# power_supplies_HVAMP.net
KiCad netlist of a schematic drawn in Altium Designer
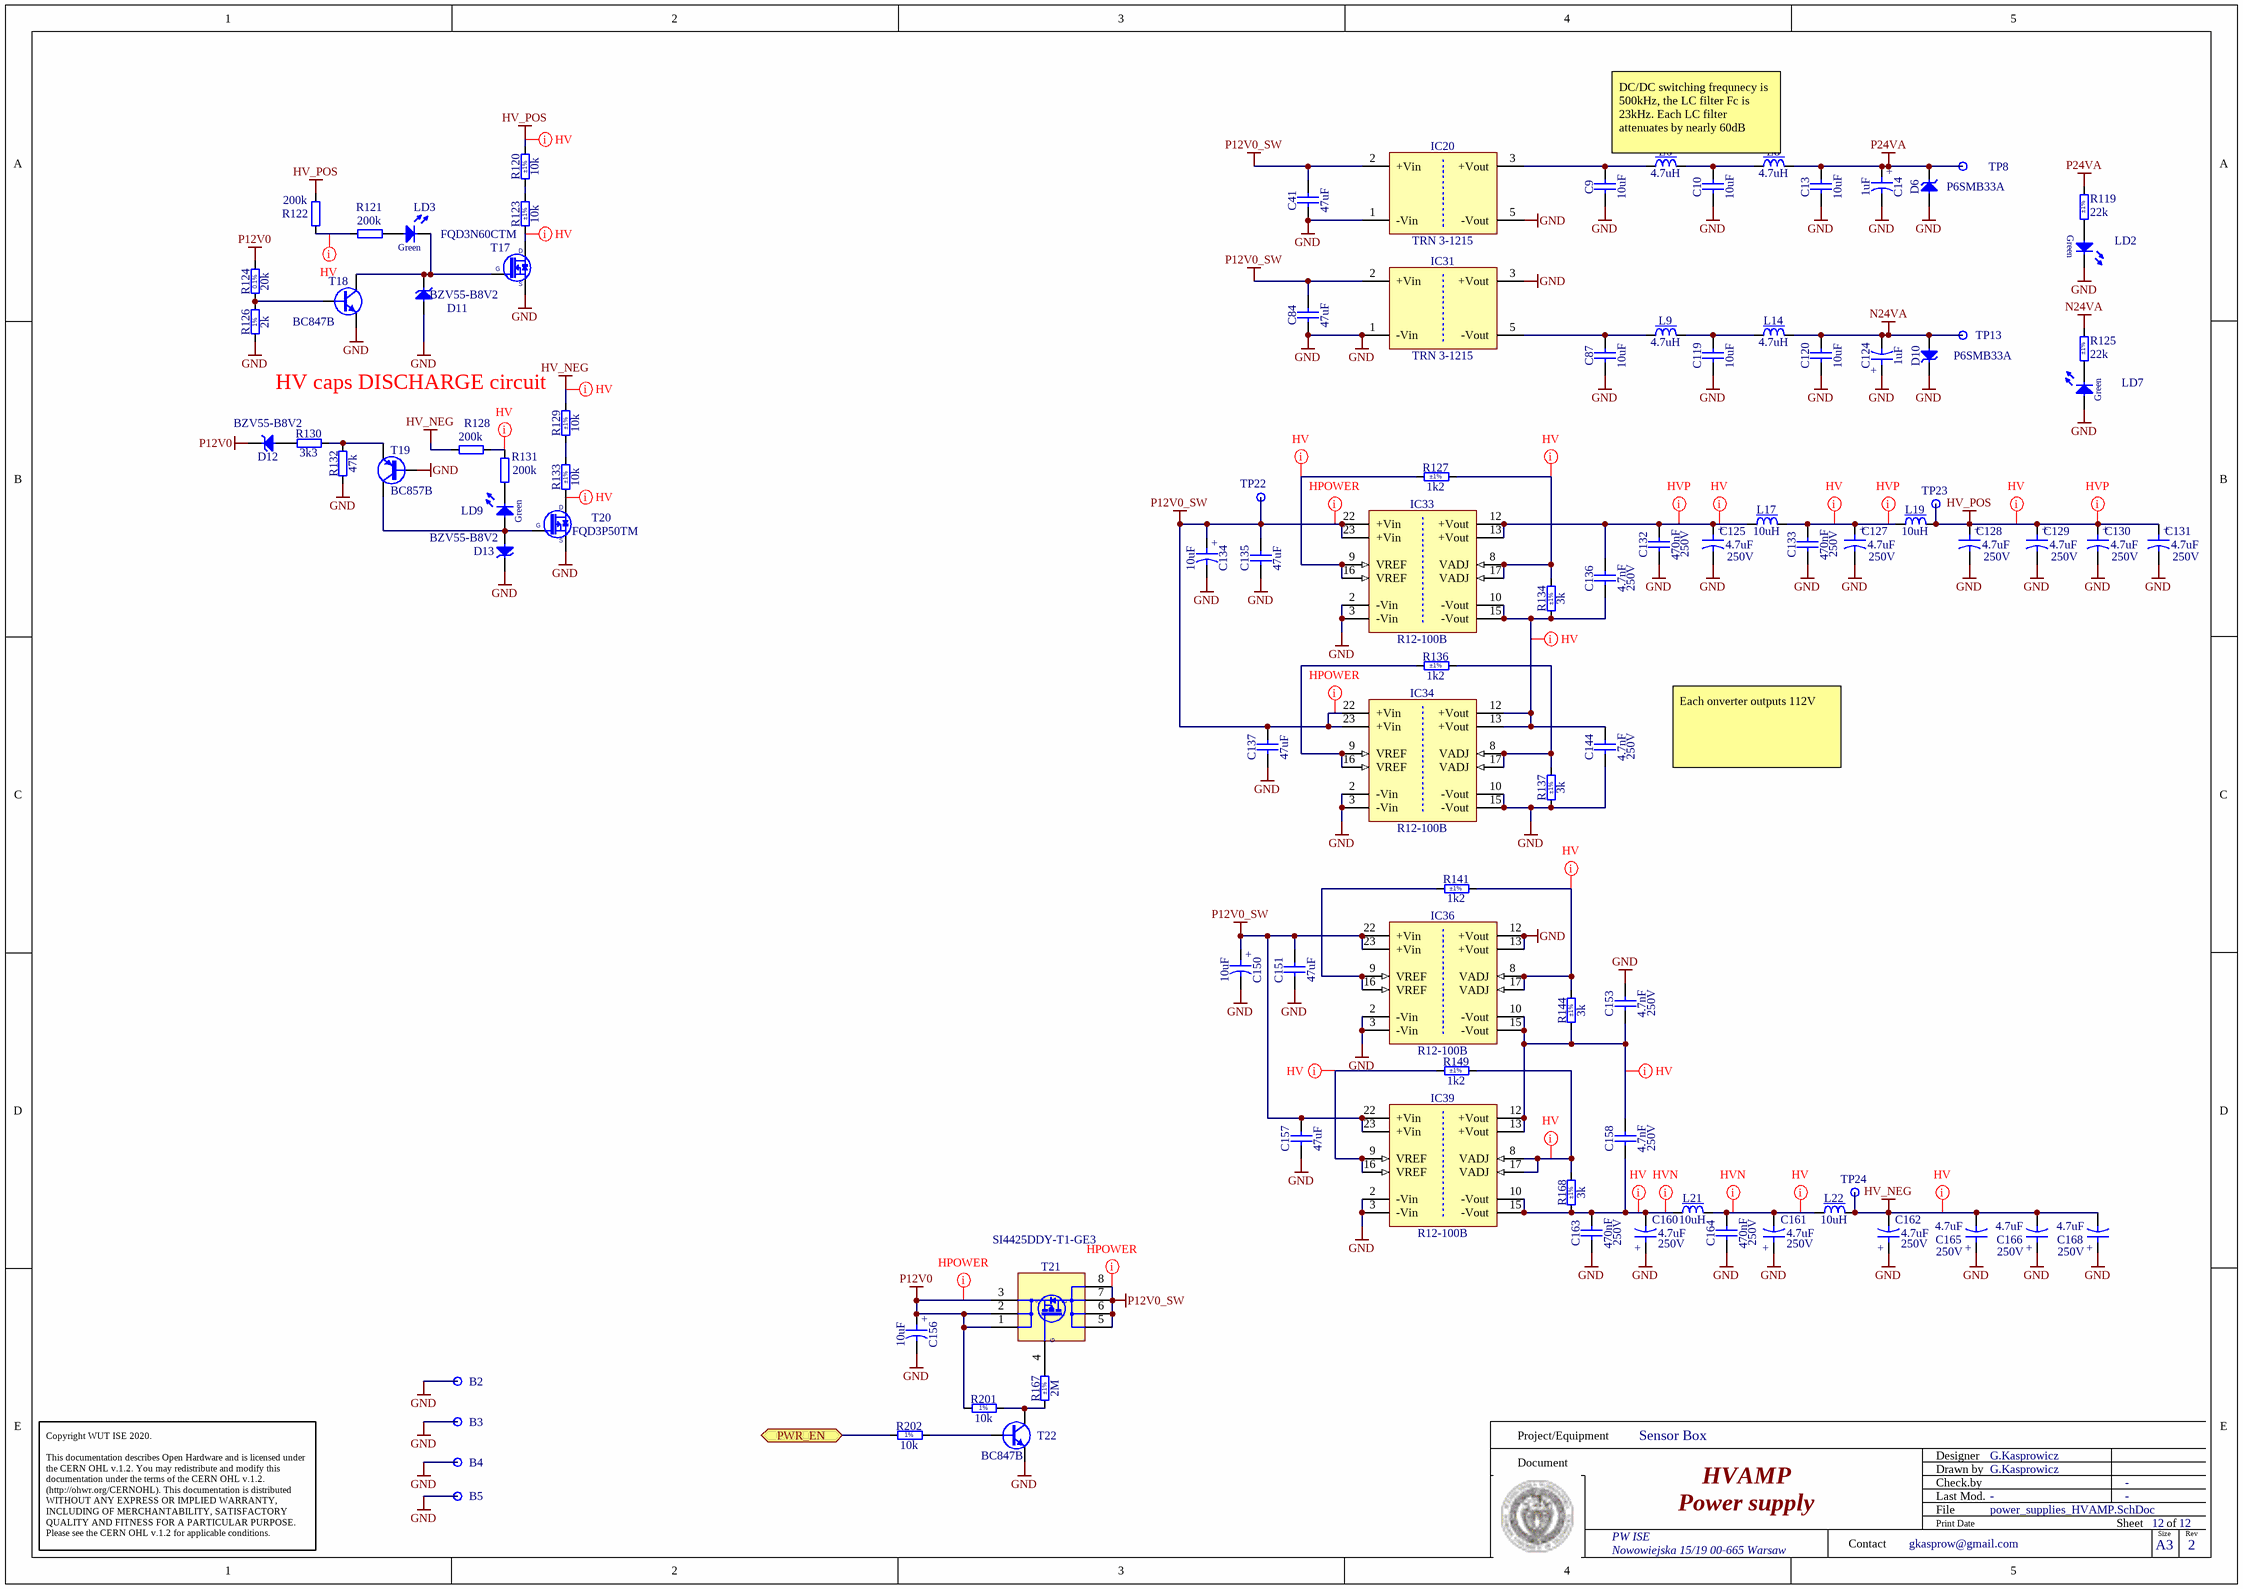
[diagram p0: power_supplies_HVAMP.SchDoc]

(export (version "E")
  (design (tool "Eeschema 10.0.6"))
  (components
    (comp (ref "B2")
      (value "Plated Hole")
      (footprint "MTG320_700")
      (description "Single Terminal Socket")
      (fields (field (name "PART NUMBER") "PLATED_HOLE3.2_PAD7.0"))
      (libsource (lib "Eletro-mechanical") (part "Single Terminal Socket"))
    )
    (comp (ref "B3")
      (value "Plated Hole")
      (footprint "MTG320_700")
      (description "Single Terminal Socket")
      (fields (field (name "PART NUMBER") "PLATED_HOLE3.2_PAD7.0"))
      (libsource (lib "Eletro-mechanical") (part "Single Terminal Socket"))
    )
    (comp (ref "B4")
      (value "Plated Hole")
      (footprint "MTG320_700")
      (description "Single Terminal Socket")
      (fields (field (name "PART NUMBER") "PLATED_HOLE3.2_PAD7.0"))
      (libsource (lib "Eletro-mechanical") (part "Single Terminal Socket"))
    )
    (comp (ref "B5")
      (value "Plated Hole")
      (footprint "MTG320_700")
      (description "Single Terminal Socket")
      (fields (field (name "PART NUMBER") "PLATED_HOLE3.2_PAD7.0"))
      (libsource (lib "Eletro-mechanical") (part "Single Terminal Socket"))
    )
    (comp (ref "C9")
      (value "10uF")
      (footprint "CAPC2012X145N")
      (description "Non-polarised capacitor")
      (fields
        (field (name "PART NUMBER") "CC0805_10UF_35V_10%_X5R_MURATA_GRM21BR6YA106KE43L")
        (field (name "VOLTAGE") "35V")
      )
      (libsource (lib "Capacitors") (part "Capacitor - non polarized"))
    )
    (comp (ref "C10")
      (value "10uF")
      (footprint "CAPC2012X145N")
      (description "Non-polarised capacitor")
      (fields
        (field (name "PART NUMBER") "CC0805_10UF_35V_10%_X5R_MURATA_GRM21BR6YA106KE43L")
        (field (name "VOLTAGE") "35V")
      )
      (libsource (lib "Capacitors") (part "Capacitor - non polarized"))
    )
    (comp (ref "C13")
      (value "10uF")
      (footprint "CAPC2012X145N")
      (description "Non-polarised capacitor")
      (fields
        (field (name "PART NUMBER") "CC0805_10UF_35V_10%_X5R_MURATA_GRM21BR6YA106KE43L")
        (field (name "VOLTAGE") "35V")
      )
      (libsource (lib "Capacitors") (part "Capacitor - non polarized"))
    )
    (comp (ref "C14")
      (value "1uF")
      (footprint "CAPMP3216X180N")
      (description "Polarised capacitor")
      (fields (field (name "PART NUMBER") "CTE3216-18_1UF_35V_10%") (field (name "VOLTAGE") "35V"))
      (libsource (lib "Capacitors") (part "Capacitor - polarized"))
    )
    (comp (ref "C41")
      (value "47uF")
      (footprint "CAPC3225X270N")
      (description "Non-polarised capacitor")
      (fields (field (name "PART NUMBER") "CC1210_47UF_16V_20%_X5R") (field (name "VOLTAGE") "16V"))
      (libsource (lib "Capacitors") (part "Capacitor - non polarized"))
    )
    (comp (ref "C84")
      (value "47uF")
      (footprint "CAPC3225X270N")
      (description "Non-polarised capacitor")
      (fields (field (name "PART NUMBER") "CC1210_47UF_16V_20%_X5R") (field (name "VOLTAGE") "16V"))
      (libsource (lib "Capacitors") (part "Capacitor - non polarized"))
    )
    (comp (ref "C87")
      (value "10uF")
      (footprint "CAPC2012X145N")
      (description "Non-polarised capacitor")
      (fields
        (field (name "PART NUMBER") "CC0805_10UF_35V_10%_X5R_MURATA_GRM21BR6YA106KE43L")
        (field (name "VOLTAGE") "35V")
      )
      (libsource (lib "Capacitors") (part "Capacitor - non polarized"))
    )
    (comp (ref "C119")
      (value "10uF")
      (footprint "CAPC2012X145N")
      (description "Non-polarised capacitor")
      (fields
        (field (name "PART NUMBER") "CC0805_10UF_35V_10%_X5R_MURATA_GRM21BR6YA106KE43L")
        (field (name "VOLTAGE") "35V")
      )
      (libsource (lib "Capacitors") (part "Capacitor - non polarized"))
    )
    (comp (ref "C120")
      (value "10uF")
      (footprint "CAPC2012X145N")
      (description "Non-polarised capacitor")
      (fields
        (field (name "PART NUMBER") "CC0805_10UF_35V_10%_X5R_MURATA_GRM21BR6YA106KE43L")
        (field (name "VOLTAGE") "35V")
      )
      (libsource (lib "Capacitors") (part "Capacitor - non polarized"))
    )
    (comp (ref "C124")
      (value "1uF")
      (footprint "CAPMP3216X180N")
      (description "Polarised capacitor")
      (fields (field (name "PART NUMBER") "CTE3216-18_1UF_35V_10%") (field (name "VOLTAGE") "35V"))
      (libsource (lib "Capacitors") (part "Capacitor - polarized"))
    )
    (comp (ref "C125")
      (value "4.7uF")
      (footprint "CAPAE9383X100M")
      (description "Electrolytic capacitor 4.7uF 250V")
      (fields
        (field (name "PART NUMBER") "CAE800-1000_4.7UF_250V_20%")
        (field (name "VOLTAGE") "250V")
        (field (name "TOLERANCE") "±20%")
      )
      (libsource (lib "Passives_RC") (part "CAP_ELECTRO_F_4.7u_250V"))
    )
    (comp (ref "C127")
      (value "4.7uF")
      (footprint "CAPAE9383X100M")
      (description "Electrolytic capacitor 4.7uF 250V")
      (fields
        (field (name "PART NUMBER") "CAE800-1000_4.7UF_250V_20%")
        (field (name "VOLTAGE") "250V")
        (field (name "TOLERANCE") "±20%")
      )
      (libsource (lib "Passives_RC") (part "CAP_ELECTRO_F_4.7u_250V"))
    )
    (comp (ref "C128")
      (value "4.7uF")
      (footprint "CAPAE9383X100M")
      (description "Electrolytic capacitor 4.7uF 250V")
      (fields
        (field (name "PART NUMBER") "CAE800-1000_4.7UF_250V_20%")
        (field (name "VOLTAGE") "250V")
        (field (name "TOLERANCE") "±20%")
      )
      (libsource (lib "Passives_RC") (part "CAP_ELECTRO_F_4.7u_250V"))
    )
    (comp (ref "C129")
      (value "4.7uF")
      (footprint "CAPAE9383X100M")
      (description "Electrolytic capacitor 4.7uF 250V")
      (fields
        (field (name "PART NUMBER") "CAE800-1000_4.7UF_250V_20%")
        (field (name "VOLTAGE") "250V")
        (field (name "TOLERANCE") "±20%")
      )
      (libsource (lib "Passives_RC") (part "CAP_ELECTRO_F_4.7u_250V"))
    )
    (comp (ref "C130")
      (value "4.7uF")
      (footprint "CAPAE9383X100M")
      (description "Electrolytic capacitor 4.7uF 250V")
      (fields
        (field (name "PART NUMBER") "CAE800-1000_4.7UF_250V_20%")
        (field (name "VOLTAGE") "250V")
        (field (name "TOLERANCE") "±20%")
      )
      (libsource (lib "Passives_RC") (part "CAP_ELECTRO_F_4.7u_250V"))
    )
    (comp (ref "C131")
      (value "4.7uF")
      (footprint "CAPAE9383X100M")
      (description "Electrolytic capacitor 4.7uF 250V")
      (fields
        (field (name "PART NUMBER") "CAE800-1000_4.7UF_250V_20%")
        (field (name "VOLTAGE") "250V")
        (field (name "TOLERANCE") "±20%")
      )
      (libsource (lib "Passives_RC") (part "CAP_ELECTRO_F_4.7u_250V"))
    )
    (comp (ref "C132")
      (value "470nF")
      (footprint "CAPC4532X185N")
      (description "Non-polarised capacitor")
      (fields
        (field (name "PART NUMBER") "CC1812_470NF_250V_10%_X7R_FT-CAP")
        (field (name "VOLTAGE") "250V")
        (field (name "TOLERANCE") "±10%")
      )
      (libsource (lib "Capacitors") (part "Capacitor - non polarized"))
    )
    (comp (ref "C133")
      (value "470nF")
      (footprint "CAPC4532X185N")
      (description "Non-polarised capacitor")
      (fields
        (field (name "PART NUMBER") "CC1812_470NF_250V_10%_X7R_FT-CAP")
        (field (name "VOLTAGE") "250V")
        (field (name "TOLERANCE") "±10%")
      )
      (libsource (lib "Capacitors") (part "Capacitor - non polarized"))
    )
    (comp (ref "C134")
      (value "10uF")
      (footprint "CAPMP6032X280N")
      (description "Polarised capacitor")
      (fields (field (name "PART NUMBER") "CTE6032-28_10UF_25V_10%_LESR0500") (field (name "VOLTAGE") "25V"))
      (libsource (lib "Capacitors") (part "Capacitor - polarized"))
    )
    (comp (ref "C135")
      (value "47uF")
      (footprint "CAPC3225X270N")
      (description "Non-polarised capacitor")
      (fields (field (name "PART NUMBER") "CC1210_47UF_16V_20%_X5R") (field (name "VOLTAGE") "16V"))
      (libsource (lib "Capacitors") (part "Capacitor - non polarized"))
    )
    (comp (ref "C136")
      (value "4.7nF")
      (footprint "CAPC2012X135N")
      (description "Non-polarised capacitor")
      (fields
        (field (name "PART NUMBER") "CC0805_4.7NF_250V_10%_X7R")
        (field (name "VOLTAGE") "250V")
        (field (name "TOLERANCE") "±10%")
      )
      (libsource (lib "Capacitors") (part "Capacitor - non polarized"))
    )
    (comp (ref "C137")
      (value "47uF")
      (footprint "CAPC3225X270N")
      (description "Non-polarised capacitor")
      (fields (field (name "PART NUMBER") "CC1210_47UF_16V_20%_X5R") (field (name "VOLTAGE") "16V"))
      (libsource (lib "Capacitors") (part "Capacitor - non polarized"))
    )
    (comp (ref "C144")
      (value "4.7nF")
      (footprint "CAPC2012X135N")
      (description "Non-polarised capacitor")
      (fields
        (field (name "PART NUMBER") "CC0805_4.7NF_250V_10%_X7R")
        (field (name "VOLTAGE") "250V")
        (field (name "TOLERANCE") "±10%")
      )
      (libsource (lib "Capacitors") (part "Capacitor - non polarized"))
    )
    (comp (ref "C150")
      (value "10uF")
      (footprint "CAPMP6032X280N")
      (description "Polarised capacitor")
      (fields (field (name "PART NUMBER") "CTE6032-28_10UF_25V_10%_LESR0500") (field (name "VOLTAGE") "25V"))
      (libsource (lib "Capacitors") (part "Capacitor - polarized"))
    )
    (comp (ref "C151")
      (value "47uF")
      (footprint "CAPC3225X270N")
      (description "Non-polarised capacitor")
      (fields (field (name "PART NUMBER") "CC1210_47UF_16V_20%_X5R") (field (name "VOLTAGE") "16V"))
      (libsource (lib "Capacitors") (part "Capacitor - non polarized"))
    )
    (comp (ref "C153")
      (value "4.7nF")
      (footprint "CAPC2012X135N")
      (description "Non-polarised capacitor")
      (fields
        (field (name "PART NUMBER") "CC0805_4.7NF_250V_10%_X7R")
        (field (name "VOLTAGE") "250V")
        (field (name "TOLERANCE") "±10%")
      )
      (libsource (lib "Capacitors") (part "Capacitor - non polarized"))
    )
    (comp (ref "C156")
      (value "10uF")
      (footprint "CAPMP6032X280N")
      (description "Polarised capacitor")
      (fields (field (name "PART NUMBER") "CTE6032-28_10UF_25V_10%_LESR0500") (field (name "VOLTAGE") "25V"))
      (libsource (lib "Capacitors") (part "Capacitor - polarized"))
    )
    (comp (ref "C157")
      (value "47uF")
      (footprint "CAPC3225X270N")
      (description "Non-polarised capacitor")
      (fields (field (name "PART NUMBER") "CC1210_47UF_16V_20%_X5R") (field (name "VOLTAGE") "16V"))
      (libsource (lib "Capacitors") (part "Capacitor - non polarized"))
    )
    (comp (ref "C158")
      (value "4.7nF")
      (footprint "CAPC2012X135N")
      (description "Non-polarised capacitor")
      (fields
        (field (name "PART NUMBER") "CC0805_4.7NF_250V_10%_X7R")
        (field (name "VOLTAGE") "250V")
        (field (name "TOLERANCE") "±10%")
      )
      (libsource (lib "Capacitors") (part "Capacitor - non polarized"))
    )
    (comp (ref "C160")
      (value "4.7uF")
      (footprint "CAPAE9383X100M")
      (description "Electrolytic capacitor 4.7uF 250V")
      (fields
        (field (name "PART NUMBER") "CAE800-1000_4.7UF_250V_20%")
        (field (name "VOLTAGE") "250V")
        (field (name "TOLERANCE") "±20%")
      )
      (libsource (lib "Passives_RC") (part "CAP_ELECTRO_F_4.7u_250V"))
    )
    (comp (ref "C161")
      (value "4.7uF")
      (footprint "CAPAE9383X100M")
      (description "Electrolytic capacitor 4.7uF 250V")
      (fields
        (field (name "PART NUMBER") "CAE800-1000_4.7UF_250V_20%")
        (field (name "VOLTAGE") "250V")
        (field (name "TOLERANCE") "±20%")
      )
      (libsource (lib "Passives_RC") (part "CAP_ELECTRO_F_4.7u_250V"))
    )
    (comp (ref "C162")
      (value "4.7uF")
      (footprint "CAPAE9383X100M")
      (description "Electrolytic capacitor 4.7uF 250V")
      (fields
        (field (name "PART NUMBER") "CAE800-1000_4.7UF_250V_20%")
        (field (name "VOLTAGE") "250V")
        (field (name "TOLERANCE") "±20%")
      )
      (libsource (lib "Passives_RC") (part "CAP_ELECTRO_F_4.7u_250V"))
    )
    (comp (ref "C163")
      (value "470nF")
      (footprint "CAPC4532X185N")
      (description "Non-polarised capacitor")
      (fields
        (field (name "PART NUMBER") "CC1812_470NF_250V_10%_X7R_FT-CAP")
        (field (name "VOLTAGE") "250V")
        (field (name "TOLERANCE") "±10%")
      )
      (libsource (lib "Capacitors") (part "Capacitor - non polarized"))
    )
    (comp (ref "C164")
      (value "470nF")
      (footprint "CAPC4532X185N")
      (description "Non-polarised capacitor")
      (fields
        (field (name "PART NUMBER") "CC1812_470NF_250V_10%_X7R_FT-CAP")
        (field (name "VOLTAGE") "250V")
        (field (name "TOLERANCE") "±10%")
      )
      (libsource (lib "Capacitors") (part "Capacitor - non polarized"))
    )
    (comp (ref "C165")
      (value "4.7uF")
      (footprint "CAPAE9383X100M")
      (description "Electrolytic capacitor 4.7uF 250V")
      (fields
        (field (name "PART NUMBER") "CAE800-1000_4.7UF_250V_20%")
        (field (name "VOLTAGE") "250V")
        (field (name "TOLERANCE") "±20%")
      )
      (libsource (lib "Passives_RC") (part "CAP_ELECTRO_F_4.7u_250V"))
    )
    (comp (ref "C166")
      (value "4.7uF")
      (footprint "CAPAE9383X100M")
      (description "Electrolytic capacitor 4.7uF 250V")
      (fields
        (field (name "PART NUMBER") "CAE800-1000_4.7UF_250V_20%")
        (field (name "VOLTAGE") "250V")
        (field (name "TOLERANCE") "±20%")
      )
      (libsource (lib "Passives_RC") (part "CAP_ELECTRO_F_4.7u_250V"))
    )
    (comp (ref "C168")
      (value "4.7uF")
      (footprint "CAPAE9383X100M")
      (description "Electrolytic capacitor 4.7uF 250V")
      (fields
        (field (name "PART NUMBER") "CAE800-1000_4.7UF_250V_20%")
        (field (name "VOLTAGE") "250V")
        (field (name "TOLERANCE") "±20%")
      )
      (libsource (lib "Passives_RC") (part "CAP_ELECTRO_F_4.7u_250V"))
    )
    (comp (ref "D6")
      (value "P6SMB33A")
      (footprint "DIOM5436X261N")
      (description "Transient Voltage Suppressor Diode (Uni-Directional)")
      (fields (field (name "VOLTAGE") "33V") (field (name "POWER") "600W"))
      (libsource (lib "ICs And Semiconductors") (part "Diode TVS Uni-Directional"))
    )
    (comp (ref "D10")
      (value "P6SMB33A")
      (footprint "DIOM5436X261N")
      (description "Transient Voltage Suppressor Diode (Uni-Directional)")
      (fields (field (name "VOLTAGE") "33V") (field (name "POWER") "600W"))
      (libsource (lib "ICs And Semiconductors") (part "Diode TVS Uni-Directional"))
    )
    (comp (ref "D11")
      (value "BZV55-B8V2")
      (footprint "DIOMELF3515N")
      (description "Zener Diode")
      (fields (field (name "VOLTAGE") "8V2") (field (name "POWER") "500mW"))
      (libsource (lib "ICs And Semiconductors") (part "Diode Zener"))
    )
    (comp (ref "D12")
      (value "BZV55-B8V2")
      (footprint "DIOMELF3515N")
      (description "Zener Diode")
      (fields (field (name "VOLTAGE") "8V2") (field (name "POWER") "500mW"))
      (libsource (lib "ICs And Semiconductors") (part "Diode Zener"))
    )
    (comp (ref "D13")
      (value "BZV55-B8V2")
      (footprint "DIOMELF3515N")
      (description "Zener Diode")
      (fields (field (name "VOLTAGE") "8V2") (field (name "POWER") "500mW"))
      (libsource (lib "ICs And Semiconductors") (part "Diode Zener"))
    )
    (comp (ref "IC20")
      (value "TRN 3-1215")
      (footprint "DCDC_TRACO_TRN3")
      (description "9-18V DC to 24V, Iout (max) 125mA, 3W DC-DC Converter")
      (fields (field (name "MANUFACTURER") "TRACO POWER"))
      (libsource (lib "Regulators_SMPS") (part "DCDC_TRACO_TRN 3-0515"))
    )
    (comp (ref "IC31")
      (value "TRN 3-1215")
      (footprint "DCDC_TRACO_TRN3")
      (description "9-18V DC to 24V, Iout (max) 125mA, 3W DC-DC Converter")
      (fields (field (name "MANUFACTURER") "TRACO POWER"))
      (libsource (lib "Regulators_SMPS") (part "DCDC_TRACO_TRN 3-0515"))
    )
    (comp (ref "IC33")
      (value "R12-100B")
      (footprint "DCDC_RECOM_Rxx-B")
      (description "RECOM, Rxx-B Series, Single Output DCDC Converter")
      (fields (field (name "MANUFACTURER") "RECOM"))
      (libsource (lib "ICs And Semiconductors") (part "DCDC_RECOM_Rxx-B_Single Output"))
    )
    (comp (ref "IC34")
      (value "R12-100B")
      (footprint "DCDC_RECOM_Rxx-B")
      (description "RECOM, Rxx-B Series, Single Output DCDC Converter")
      (fields (field (name "MANUFACTURER") "RECOM"))
      (libsource (lib "ICs And Semiconductors") (part "DCDC_RECOM_Rxx-B_Single Output"))
    )
    (comp (ref "IC36")
      (value "R12-100B")
      (footprint "DCDC_RECOM_Rxx-B")
      (description "RECOM, Rxx-B Series, Single Output DCDC Converter")
      (fields (field (name "MANUFACTURER") "RECOM"))
      (libsource (lib "ICs And Semiconductors") (part "DCDC_RECOM_Rxx-B_Single Output"))
    )
    (comp (ref "IC39")
      (value "R12-100B")
      (footprint "DCDC_RECOM_Rxx-B")
      (description "RECOM, Rxx-B Series, Single Output DCDC Converter")
      (fields (field (name "MANUFACTURER") "RECOM"))
      (libsource (lib "ICs And Semiconductors") (part "DCDC_RECOM_Rxx-B_Single Output"))
    )
    (comp (ref "L6")
      (value "4.7uH")
      (footprint "INDC2012X145N")
      (description "Inductor With Core")
      (fields (field (name "PART NUMBER") "IND0805_4.7UH_20%_TAIYO-YUDEN_CB") (field (name "POWER") "300mA"))
      (libsource (lib "Inductors & Transformers") (part "Inductor With Magnetic core"))
    )
    (comp (ref "L8")
      (value "4.7uH")
      (footprint "INDC2012X145N")
      (description "Inductor With Core")
      (fields (field (name "PART NUMBER") "IND0805_4.7UH_20%_TAIYO-YUDEN_CB") (field (name "POWER") "300mA"))
      (libsource (lib "Inductors & Transformers") (part "Inductor With Magnetic core"))
    )
    (comp (ref "L9")
      (value "4.7uH")
      (footprint "INDC2012X145N")
      (description "Inductor With Core")
      (fields (field (name "PART NUMBER") "IND0805_4.7UH_20%_TAIYO-YUDEN_CB") (field (name "POWER") "300mA"))
      (libsource (lib "Inductors & Transformers") (part "Inductor With Magnetic core"))
    )
    (comp (ref "L14")
      (value "4.7uH")
      (footprint "INDC2012X145N")
      (description "Inductor With Core")
      (fields (field (name "PART NUMBER") "IND0805_4.7UH_20%_TAIYO-YUDEN_CB") (field (name "POWER") "300mA"))
      (libsource (lib "Inductors & Transformers") (part "Inductor With Magnetic core"))
    )
    (comp (ref "L17")
      (value "10uH")
      (footprint "IND_MURATA-PS_8400")
      (description "Inductor With Core")
      (fields (field (name "PART NUMBER") "IND_10UH_10%_MURATA-PS_8400") (field (name "POWER") "950mA"))
      (libsource (lib "Inductors & Transformers") (part "Inductor With Magnetic core"))
    )
    (comp (ref "L19")
      (value "10uH")
      (footprint "IND_MURATA-PS_8400")
      (description "Inductor With Core")
      (fields (field (name "PART NUMBER") "IND_10UH_10%_MURATA-PS_8400") (field (name "POWER") "950mA"))
      (libsource (lib "Inductors & Transformers") (part "Inductor With Magnetic core"))
    )
    (comp (ref "L21")
      (value "10uH")
      (footprint "IND_MURATA-PS_8400")
      (description "Inductor With Core")
      (fields (field (name "PART NUMBER") "IND_10UH_10%_MURATA-PS_8400") (field (name "POWER") "950mA"))
      (libsource (lib "Inductors & Transformers") (part "Inductor With Magnetic core"))
    )
    (comp (ref "L22")
      (value "10uH")
      (footprint "IND_MURATA-PS_8400")
      (description "Inductor With Core")
      (fields (field (name "PART NUMBER") "IND_10UH_10%_MURATA-PS_8400") (field (name "POWER") "950mA"))
      (libsource (lib "Inductors & Transformers") (part "Inductor With Magnetic core"))
    )
    (comp (ref "LD2")
      (value "Green")
      (footprint "LED_KINGBRIGHT_KPH-1608CGCKr")
      (description "Green 0603")
      (fields
        (field (name "PART NUMBER") "LED_KINGBRIGHT_KPH-1608CGCK")
        (field (name "MANUFACTURER") "KINGBRIGHT")
      )
      (libsource (lib "LIBRARY_SCH") (part "LED_0603_Green"))
    )
    (comp (ref "LD3")
      (value "Green")
      (footprint "LED_KINGBRIGHT_KPH-1608CGCKr")
      (description "Green 0603")
      (fields
        (field (name "PART NUMBER") "LED_KINGBRIGHT_KPH-1608CGCK")
        (field (name "MANUFACTURER") "KINGBRIGHT")
      )
      (libsource (lib "LIBRARY_SCH") (part "LED_0603_Green"))
    )
    (comp (ref "LD7")
      (value "Green")
      (footprint "LED_KINGBRIGHT_KPH-1608CGCKr")
      (description "Green 0603")
      (fields
        (field (name "PART NUMBER") "LED_KINGBRIGHT_KPH-1608CGCK")
        (field (name "MANUFACTURER") "KINGBRIGHT")
      )
      (libsource (lib "LIBRARY_SCH") (part "LED_0603_Green"))
    )
    (comp (ref "LD9")
      (value "Green")
      (footprint "LED_KINGBRIGHT_KPH-1608CGCKr")
      (description "Green 0603")
      (fields
        (field (name "PART NUMBER") "LED_KINGBRIGHT_KPH-1608CGCK")
        (field (name "MANUFACTURER") "KINGBRIGHT")
      )
      (libsource (lib "LIBRARY_SCH") (part "LED_0603_Green"))
    )
    (comp (ref "R119")
      (value "22k")
      (footprint "RESC1005X40N")
      (description "Resistor - 1%")
      (fields
        (field (name "PART NUMBER") "R0402_22K_1%_0.0625W_100PPM")
        (field (name "POWER") "0.0625W")
        (field (name "TOLERANCE") "±1%")
      )
      (libsource (lib "Resistors") (part "Resistor - 1%"))
    )
    (comp (ref "R120")
      (value "10k")
      (footprint "RESC3216X65N")
      (description "Resistor - 1%")
      (fields
        (field (name "TOLERANCE") "±1%")
        (field (name "PART NUMBER") "R1206_10K_1%_0.25W_100PPM")
        (field (name "POWER") "0.25W")
      )
      (libsource (lib "Resistors") (part "Resistor - 1%"))
    )
    (comp (ref "R121")
      (value "200k")
      (footprint "RESC3216X65N")
      (description "Resistor - 1%")
      (fields (field (name "PART NUMBER") "R1206_200K_1%_0.25W_100PPM") (field (name "POWER") "0.25W"))
      (libsource (lib "Resistors") (part "Resistor - 1%"))
    )
    (comp (ref "R122")
      (value "200k")
      (footprint "RESC3216X65N")
      (description "Resistor - 1%")
      (fields (field (name "PART NUMBER") "R1206_200K_1%_0.25W_100PPM") (field (name "POWER") "0.25W"))
      (libsource (lib "Resistors") (part "Resistor - 1%"))
    )
    (comp (ref "R123")
      (value "10k")
      (footprint "RESC3216X65N")
      (description "Resistor - 1%")
      (fields
        (field (name "TOLERANCE") "±1%")
        (field (name "PART NUMBER") "R1206_10K_1%_0.25W_100PPM")
        (field (name "POWER") "0.25W")
      )
      (libsource (lib "Resistors") (part "Resistor - 1%"))
    )
    (comp (ref "R124")
      (value "20k")
      (footprint "RESC1608X55N")
      (description "Resistor - 0.1%")
      (fields (field (name "PART NUMBER") "R0603_20K_0.1%_0.063W_10PPM") (field (name "POWER") "0.063W"))
      (libsource (lib "Resistors") (part "Resistor - 0.1%"))
    )
    (comp (ref "R125")
      (value "22k")
      (footprint "RESC1005X40N")
      (description "Resistor - 1%")
      (fields
        (field (name "PART NUMBER") "R0402_22K_1%_0.0625W_100PPM")
        (field (name "POWER") "0.0625W")
        (field (name "TOLERANCE") "±1%")
      )
      (libsource (lib "Resistors") (part "Resistor - 1%"))
    )
    (comp (ref "R126")
      (value "2k")
      (footprint "RESC1005X40N")
      (description "Resistor - 1%")
      (fields (field (name "PART NUMBER") "R0402_2K_1%_0.0625W_100PPM") (field (name "POWER") "0.0625W"))
      (libsource (lib "") (part "Resistor - 1%_1"))
    )
    (comp (ref "R127")
      (value "1k2")
      (footprint "RESC1608X55N")
      (description "Resistor - 1%")
      (fields
        (field (name "TOLERANCE") "±1%")
        (field (name "PART NUMBER") "R0603_1K2_1%_0.1W_100PPM")
        (field (name "POWER") "0.1W")
      )
      (libsource (lib "Resistors") (part "Resistor - 1%"))
    )
    (comp (ref "R128")
      (value "200k")
      (footprint "RESC3216X65N")
      (description "Resistor - 1%")
      (fields (field (name "PART NUMBER") "R1206_200K_1%_0.25W_100PPM") (field (name "POWER") "0.25W"))
      (libsource (lib "Resistors") (part "Resistor - 1%"))
    )
    (comp (ref "R129")
      (value "10k")
      (footprint "RESC3216X65N")
      (description "Resistor - 1%")
      (fields
        (field (name "TOLERANCE") "±1%")
        (field (name "PART NUMBER") "R1206_10K_1%_0.25W_100PPM")
        (field (name "POWER") "0.25W")
      )
      (libsource (lib "Resistors") (part "Resistor - 1%"))
    )
    (comp (ref "R130")
      (value "3k3")
      (footprint "RESC1005X40N")
      (description "Resistor - 1%")
      (fields (field (name "PART NUMBER") "R0402_3K3_1%_0.0625W_100PPM") (field (name "POWER") "0.0625W"))
      (libsource (lib "Resistors") (part "Resistor - 1%"))
    )
    (comp (ref "R131")
      (value "200k")
      (footprint "RESC3216X65N")
      (description "Resistor - 1%")
      (fields (field (name "PART NUMBER") "R1206_200K_1%_0.25W_100PPM") (field (name "POWER") "0.25W"))
      (libsource (lib "Resistors") (part "Resistor - 1%"))
    )
    (comp (ref "R132")
      (value "47k")
      (footprint "RESC1608X55N")
      (description "Resistor - 1%")
      (fields (field (name "PART NUMBER") "R0603_47K_1%_0.1W_100PPM") (field (name "POWER") "0.1W"))
      (libsource (lib "Resistors") (part "Resistor - 1%"))
    )
    (comp (ref "R133")
      (value "10k")
      (footprint "RESC3216X65N")
      (description "Resistor - 1%")
      (fields
        (field (name "TOLERANCE") "±1%")
        (field (name "PART NUMBER") "R1206_10K_1%_0.25W_100PPM")
        (field (name "POWER") "0.25W")
      )
      (libsource (lib "Resistors") (part "Resistor - 1%"))
    )
    (comp (ref "R134")
      (value "3k")
      (footprint "RESC1608X55N")
      (description "Resistor - 1%")
      (fields
        (field (name "TOLERANCE") "±1%")
        (field (name "PART NUMBER") "R0603_3K_1%_0.1W_100PPM")
        (field (name "POWER") "0.1W")
      )
      (libsource (lib "Resistors") (part "Resistor - 1%"))
    )
    (comp (ref "R136")
      (value "1k2")
      (footprint "RESC1608X55N")
      (description "Resistor - 1%")
      (fields
        (field (name "TOLERANCE") "±1%")
        (field (name "PART NUMBER") "R0603_1K2_1%_0.1W_100PPM")
        (field (name "POWER") "0.1W")
      )
      (libsource (lib "Resistors") (part "Resistor - 1%"))
    )
    (comp (ref "R137")
      (value "3k")
      (footprint "RESC1608X55N")
      (description "Resistor - 1%")
      (fields
        (field (name "TOLERANCE") "±1%")
        (field (name "PART NUMBER") "R0603_3K_1%_0.1W_100PPM")
        (field (name "POWER") "0.1W")
      )
      (libsource (lib "Resistors") (part "Resistor - 1%"))
    )
    (comp (ref "R141")
      (value "1k2")
      (footprint "RESC1608X55N")
      (description "Resistor - 1%")
      (fields
        (field (name "TOLERANCE") "±1%")
        (field (name "PART NUMBER") "R0603_1K2_1%_0.1W_100PPM")
        (field (name "POWER") "0.1W")
      )
      (libsource (lib "Resistors") (part "Resistor - 1%"))
    )
    (comp (ref "R144")
      (value "3k")
      (footprint "RESC1608X55N")
      (description "Resistor - 1%")
      (fields
        (field (name "TOLERANCE") "±1%")
        (field (name "PART NUMBER") "R0603_3K_1%_0.1W_100PPM")
        (field (name "POWER") "0.1W")
      )
      (libsource (lib "Resistors") (part "Resistor - 1%"))
    )
    (comp (ref "R149")
      (value "1k2")
      (footprint "RESC1608X55N")
      (description "Resistor - 1%")
      (fields
        (field (name "TOLERANCE") "±1%")
        (field (name "PART NUMBER") "R0603_1K2_1%_0.1W_100PPM")
        (field (name "POWER") "0.1W")
      )
      (libsource (lib "Resistors") (part "Resistor - 1%"))
    )
    (comp (ref "R167")
      (value "2M")
      (footprint "RESC1005X40N")
      (description "Resistor - 1%")
      (fields
        (field (name "TOLERANCE") "±1%")
        (field (name "PART NUMBER") "R0402_2M_1%_0.0625W_100PPM")
        (field (name "POWER") "0.0625W")
      )
      (libsource (lib "Resistors") (part "Resistor - 1%"))
    )
    (comp (ref "R168")
      (value "3k")
      (footprint "RESC1608X55N")
      (description "Resistor - 1%")
      (fields
        (field (name "TOLERANCE") "±1%")
        (field (name "PART NUMBER") "R0603_3K_1%_0.1W_100PPM")
        (field (name "POWER") "0.1W")
      )
      (libsource (lib "Resistors") (part "Resistor - 1%"))
    )
    (comp (ref "R201")
      (value "10k")
      (footprint "RESC1005X40N")
      (description "Resistor - 1%")
      (fields (field (name "PART NUMBER") "R0402_10K_1%_0.0625W_100PPM") (field (name "POWER") "0.0625W"))
      (libsource (lib "") (part "Resistor - 1%_1"))
    )
    (comp (ref "R202")
      (value "10k")
      (footprint "RESC1005X40N")
      (description "Resistor - 1%")
      (fields (field (name "PART NUMBER") "R0402_10K_1%_0.0625W_100PPM") (field (name "POWER") "0.0625W"))
      (libsource (lib "") (part "Resistor - 1%_1"))
    )
    (comp (ref "T17")
      (value "FQD3N60CTM")
      (footprint "TO228P991X239-3N-R552X520")
      (description "N-CHANNEL 600V, 2.4A, 3.4Ohm")
      (fields (field (name "MANUFACTURER") "ONSEMI"))
      (libsource (lib "Tranistors_Thyristors") (part "Q_FQD3N60CTM"))
    )
    (comp (ref "T18")
      (value "BC847B")
      (footprint "SOT95P230X110-3N")
      (description "NPN Transistor")
      (fields (field (name "MANUFACTURER") "NXP SEMICONDUCTORS"))
      (libsource (lib "ICs And Semiconductors") (part "NPN B1 E2 C3"))
    )
    (comp (ref "T19")
      (value "BC857B")
      (footprint "SOT95P230X110-3N")
      (description "PNP Transistor")
      (fields (field (name "MANUFACTURER") "NXP SEMICONDUCTORS"))
      (libsource (lib "ICs And Semiconductors") (part "PNP B1 E2 C3"))
    )
    (comp (ref "T20")
      (value "FQD3P50TM")
      (footprint "TO228P991X239-3N-R552X520")
      (description "P-CHANNEL -500V, -2.1A 4.9Ohm")
      (fields (field (name "MANUFACTURER") "ONSEMI"))
      (libsource (lib "Tranistors_Thyristors") (part "Q_FQD3P50TM"))
    )
    (comp (ref "T21")
      (value "SI4425DDY-T1-GE3")
      (footprint "SOIC127P600X175-8N")
      (description "-30V -19.7A P-Channel MOSFET")
      (fields (field (name "MANUFACTURER") "VISHAY SILICONIX"))
      (libsource (lib "ICs And Semiconductors") (part "SI4425DDY"))
    )
    (comp (ref "T22")
      (value "BC847B")
      (footprint "SOT95P230X110-3N")
      (description "NPN Transistor")
      (fields (field (name "MANUFACTURER") "NXP SEMICONDUCTORS"))
      (libsource (lib "ICs And Semiconductors") (part "NPN B1 E2 C3"))
    )
    (comp (ref "TP8")
      (value "Test Point")
      (footprint "TPS127")
      (fields (field (name "PART NUMBER") "SMD_PAD_1.27X1.27MM"))
      (libsource (lib "Eletro-mechanical") (part "Test Point"))
    )
    (comp (ref "TP13")
      (value "Test Point")
      (footprint "TPS127")
      (fields (field (name "PART NUMBER") "SMD_PAD_1.27X1.27MM"))
      (libsource (lib "Eletro-mechanical") (part "Test Point"))
    )
    (comp (ref "TP22")
      (value "Test Point")
      (footprint "TPS127")
      (fields (field (name "PART NUMBER") "SMD_PAD_1.27X1.27MM"))
      (libsource (lib "Eletro-mechanical") (part "Test Point"))
    )
    (comp (ref "TP23")
      (value "Test Point")
      (footprint "TPS127")
      (fields (field (name "PART NUMBER") "SMD_PAD_1.27X1.27MM"))
      (libsource (lib "Eletro-mechanical") (part "Test Point"))
    )
    (comp (ref "TP24")
      (value "Test Point")
      (footprint "TPS127")
      (fields (field (name "PART NUMBER") "SMD_PAD_1.27X1.27MM"))
      (libsource (lib "Eletro-mechanical") (part "Test Point"))
    )
  )
  (nets
    (net (code "1") (name "/PWR_EN") (class "Default")
      (node (ref "R202") (pin "1") (pinfunction "1_1") (pintype "passive"))
    )
    (net (code "2") (name "GND") (class "Default")
      (node (ref "B2") (pin "1") (pinfunction "1_1") (pintype "bidirectional"))
      (node (ref "B3") (pin "1") (pinfunction "1_1") (pintype "bidirectional"))
      (node (ref "B4") (pin "1") (pinfunction "1_1") (pintype "bidirectional"))
      (node (ref "B5") (pin "1") (pinfunction "1_1") (pintype "bidirectional"))
      (node (ref "C10") (pin "1") (pinfunction "1_1") (pintype "passive"))
      (node (ref "C119") (pin "1") (pinfunction "1_1") (pintype "passive"))
      (node (ref "C120") (pin "1") (pinfunction "1_1") (pintype "passive"))
      (node (ref "C124") (pin "1") (pinfunction "1_1") (pintype "passive"))
      (node (ref "C125") (pin "2") (pinfunction "2_2") (pintype "passive"))
      (node (ref "C127") (pin "2") (pinfunction "2_2") (pintype "passive"))
      (node (ref "C128") (pin "2") (pinfunction "2_2") (pintype "passive"))
      (node (ref "C129") (pin "2") (pinfunction "2_2") (pintype "passive"))
      (node (ref "C13") (pin "1") (pinfunction "1_1") (pintype "passive"))
      (node (ref "C130") (pin "2") (pinfunction "2_2") (pintype "passive"))
      (node (ref "C131") (pin "2") (pinfunction "2_2") (pintype "passive"))
      (node (ref "C132") (pin "1") (pinfunction "1_1") (pintype "passive"))
      (node (ref "C133") (pin "1") (pinfunction "1_1") (pintype "passive"))
      (node (ref "C134") (pin "2") (pinfunction "2_2") (pintype "passive"))
      (node (ref "C135") (pin "1") (pinfunction "1_1") (pintype "passive"))
      (node (ref "C137") (pin "1") (pinfunction "1_1") (pintype "passive"))
      (node (ref "C14") (pin "2") (pinfunction "2_2") (pintype "passive"))
      (node (ref "C144") (pin "1") (pinfunction "1_1") (pintype "passive"))
      (node (ref "C150") (pin "2") (pinfunction "2_2") (pintype "passive"))
      (node (ref "C151") (pin "1") (pinfunction "1_1") (pintype "passive"))
      (node (ref "C153") (pin "2") (pinfunction "2_2") (pintype "passive"))
      (node (ref "C156") (pin "2") (pinfunction "2_2") (pintype "passive"))
      (node (ref "C157") (pin "1") (pinfunction "1_1") (pintype "passive"))
      (node (ref "C160") (pin "1") (pinfunction "1_1") (pintype "passive"))
      (node (ref "C161") (pin "1") (pinfunction "1_1") (pintype "passive"))
      (node (ref "C162") (pin "1") (pinfunction "1_1") (pintype "passive"))
      (node (ref "C163") (pin "1") (pinfunction "1_1") (pintype "passive"))
      (node (ref "C164") (pin "1") (pinfunction "1_1") (pintype "passive"))
      (node (ref "C165") (pin "1") (pinfunction "1_1") (pintype "passive"))
      (node (ref "C166") (pin "1") (pinfunction "1_1") (pintype "passive"))
      (node (ref "C168") (pin "1") (pinfunction "1_1") (pintype "passive"))
      (node (ref "C41") (pin "1") (pinfunction "1_1") (pintype "passive"))
      (node (ref "C84") (pin "1") (pinfunction "1_1") (pintype "passive"))
      (node (ref "C87") (pin "1") (pinfunction "1_1") (pintype "passive"))
      (node (ref "C9") (pin "1") (pinfunction "1_1") (pintype "passive"))
      (node (ref "D10") (pin "1") (pinfunction "C_1") (pintype "passive"))
      (node (ref "D11") (pin "2") (pinfunction "A_2") (pintype "passive"))
      (node (ref "D13") (pin "1") (pinfunction "C_1") (pintype "passive"))
      (node (ref "D6") (pin "2") (pinfunction "A_2") (pintype "passive"))
      (node (ref "IC20") (pin "1") (pinfunction "-Vin_1") (pintype "power_in"))
      (node (ref "IC20") (pin "5") (pinfunction "-Vout_5") (pintype "power_in"))
      (node (ref "IC31") (pin "1") (pinfunction "-Vin_1") (pintype "power_in"))
      (node (ref "IC31") (pin "3") (pinfunction "+Vout_3") (pintype "power_in"))
      (node (ref "IC33") (pin "2") (pinfunction "-Vin_2") (pintype "power_in"))
      (node (ref "IC33") (pin "3") (pinfunction "-Vin_3") (pintype "power_in"))
      (node (ref "IC34") (pin "10") (pinfunction "-Vout_10") (pintype "power_in"))
      (node (ref "IC34") (pin "15") (pinfunction "-Vout_15") (pintype "power_in"))
      (node (ref "IC34") (pin "2") (pinfunction "-Vin_2") (pintype "power_in"))
      (node (ref "IC34") (pin "3") (pinfunction "-Vin_3") (pintype "power_in"))
      (node (ref "IC36") (pin "12") (pinfunction "+Vout_12") (pintype "power_in"))
      (node (ref "IC36") (pin "13") (pinfunction "+Vout_13") (pintype "power_in"))
      (node (ref "IC36") (pin "2") (pinfunction "-Vin_2") (pintype "power_in"))
      (node (ref "IC36") (pin "3") (pinfunction "-Vin_3") (pintype "power_in"))
      (node (ref "IC39") (pin "2") (pinfunction "-Vin_2") (pintype "power_in"))
      (node (ref "IC39") (pin "3") (pinfunction "-Vin_3") (pintype "power_in"))
      (node (ref "LD2") (pin "1") (pinfunction "C_1") (pintype "passive"))
      (node (ref "LD7") (pin "2") (pinfunction "A_2") (pintype "passive"))
      (node (ref "R126") (pin "1") (pinfunction "1_1") (pintype "passive"))
      (node (ref "R132") (pin "1") (pinfunction "1_1") (pintype "passive"))
      (node (ref "R137") (pin "1") (pinfunction "1_1") (pintype "passive"))
      (node (ref "T17") (pin "2") (pinfunction "S_2") (pintype "passive"))
      (node (ref "T18") (pin "2") (pinfunction "E_2") (pintype "passive"))
      (node (ref "T19") (pin "1") (pinfunction "B_1") (pintype "passive"))
      (node (ref "T20") (pin "2") (pinfunction "S_2") (pintype "passive"))
      (node (ref "T22") (pin "2") (pinfunction "E_2") (pintype "passive"))
    )
    (net (code "3") (name "HV_NEG") (class "Default")
      (node (ref "C162") (pin "2") (pinfunction "2_2") (pintype "passive"))
      (node (ref "C165") (pin "2") (pinfunction "2_2") (pintype "passive"))
      (node (ref "C166") (pin "2") (pinfunction "2_2") (pintype "passive"))
      (node (ref "C168") (pin "2") (pinfunction "2_2") (pintype "passive"))
      (node (ref "L22") (pin "2") (pinfunction "2_2") (pintype "passive"))
      (node (ref "R128") (pin "1") (pinfunction "1_1") (pintype "passive"))
      (node (ref "R129") (pin "2") (pinfunction "2_2") (pintype "passive"))
      (node (ref "TP24") (pin "1") (pinfunction "1_1") (pintype "bidirectional"))
    )
    (net (code "4") (name "HV_POS") (class "Default")
      (node (ref "C128") (pin "1") (pinfunction "1_1") (pintype "passive"))
      (node (ref "C129") (pin "1") (pinfunction "1_1") (pintype "passive"))
      (node (ref "C130") (pin "1") (pinfunction "1_1") (pintype "passive"))
      (node (ref "C131") (pin "1") (pinfunction "1_1") (pintype "passive"))
      (node (ref "L19") (pin "2") (pinfunction "2_2") (pintype "passive"))
      (node (ref "R120") (pin "2") (pinfunction "2_2") (pintype "passive"))
      (node (ref "R122") (pin "2") (pinfunction "2_2") (pintype "passive"))
      (node (ref "TP23") (pin "1") (pinfunction "1_1") (pintype "bidirectional"))
    )
    (net (code "5") (name "N24VA") (class "Default")
      (node (ref "C120") (pin "2") (pinfunction "2_2") (pintype "passive"))
      (node (ref "C124") (pin "2") (pinfunction "2_2") (pintype "passive"))
      (node (ref "D10") (pin "2") (pinfunction "A_2") (pintype "passive"))
      (node (ref "L14") (pin "2") (pinfunction "2_2") (pintype "passive"))
      (node (ref "R125") (pin "2") (pinfunction "2_2") (pintype "passive"))
      (node (ref "TP13") (pin "1") (pinfunction "1_1") (pintype "bidirectional"))
    )
    (net (code "6") (name "Net-(C10-Pad2)") (class "Default")
      (node (ref "C10") (pin "2") (pinfunction "2_2") (pintype "passive"))
      (node (ref "L6") (pin "2") (pinfunction "2_2") (pintype "passive"))
      (node (ref "L8") (pin "1") (pinfunction "1_1") (pintype "passive"))
    )
    (net (code "7") (name "Net-(C119-Pad2)") (class "Default")
      (node (ref "C119") (pin "2") (pinfunction "2_2") (pintype "passive"))
      (node (ref "L14") (pin "1") (pinfunction "1_1") (pintype "passive"))
      (node (ref "L9") (pin "2") (pinfunction "2_2") (pintype "passive"))
    )
    (net (code "8") (name "Net-(C125-Pad1)") (class "Default")
      (node (ref "C125") (pin "1") (pinfunction "1_1") (pintype "passive"))
      (node (ref "C132") (pin "2") (pinfunction "2_2") (pintype "passive"))
      (node (ref "C136") (pin "2") (pinfunction "2_2") (pintype "passive"))
      (node (ref "IC33") (pin "12") (pinfunction "+Vout_12") (pintype "power_in"))
      (node (ref "IC33") (pin "13") (pinfunction "+Vout_13") (pintype "power_in"))
      (node (ref "L17") (pin "1") (pinfunction "1_1") (pintype "passive"))
    )
    (net (code "9") (name "Net-(C127-Pad1)") (class "Default")
      (node (ref "C127") (pin "1") (pinfunction "1_1") (pintype "passive"))
      (node (ref "C133") (pin "2") (pinfunction "2_2") (pintype "passive"))
      (node (ref "L17") (pin "2") (pinfunction "2_2") (pintype "passive"))
      (node (ref "L19") (pin "1") (pinfunction "1_1") (pintype "passive"))
    )
    (net (code "10") (name "Net-(C136-Pad1)") (class "Default")
      (node (ref "C136") (pin "1") (pinfunction "1_1") (pintype "passive"))
      (node (ref "C144") (pin "2") (pinfunction "2_2") (pintype "passive"))
      (node (ref "IC33") (pin "10") (pinfunction "-Vout_10") (pintype "power_in"))
      (node (ref "IC33") (pin "15") (pinfunction "-Vout_15") (pintype "power_in"))
      (node (ref "IC34") (pin "12") (pinfunction "+Vout_12") (pintype "power_in"))
      (node (ref "IC34") (pin "13") (pinfunction "+Vout_13") (pintype "power_in"))
      (node (ref "R134") (pin "1") (pinfunction "1_1") (pintype "passive"))
    )
    (net (code "11") (name "Net-(C153-Pad1)") (class "Default")
      (node (ref "C153") (pin "1") (pinfunction "1_1") (pintype "passive"))
      (node (ref "C158") (pin "2") (pinfunction "2_2") (pintype "passive"))
      (node (ref "IC36") (pin "10") (pinfunction "-Vout_10") (pintype "power_in"))
      (node (ref "IC36") (pin "15") (pinfunction "-Vout_15") (pintype "power_in"))
      (node (ref "IC39") (pin "12") (pinfunction "+Vout_12") (pintype "power_in"))
      (node (ref "IC39") (pin "13") (pinfunction "+Vout_13") (pintype "power_in"))
      (node (ref "R144") (pin "1") (pinfunction "1_1") (pintype "passive"))
    )
    (net (code "12") (name "Net-(C158-Pad1)") (class "Default")
      (node (ref "C158") (pin "1") (pinfunction "1_1") (pintype "passive"))
      (node (ref "C160") (pin "2") (pinfunction "2_2") (pintype "passive"))
      (node (ref "C163") (pin "2") (pinfunction "2_2") (pintype "passive"))
      (node (ref "IC39") (pin "10") (pinfunction "-Vout_10") (pintype "power_in"))
      (node (ref "IC39") (pin "15") (pinfunction "-Vout_15") (pintype "power_in"))
      (node (ref "L21") (pin "1") (pinfunction "1_1") (pintype "passive"))
      (node (ref "R168") (pin "1") (pinfunction "1_1") (pintype "passive"))
    )
    (net (code "13") (name "Net-(C161-Pad2)") (class "Default")
      (node (ref "C161") (pin "2") (pinfunction "2_2") (pintype "passive"))
      (node (ref "C164") (pin "2") (pinfunction "2_2") (pintype "passive"))
      (node (ref "L21") (pin "2") (pinfunction "2_2") (pintype "passive"))
      (node (ref "L22") (pin "1") (pinfunction "1_1") (pintype "passive"))
    )
    (net (code "14") (name "Net-(D11-C)") (class "Default")
      (node (ref "D11") (pin "1") (pinfunction "C_1") (pintype "passive"))
      (node (ref "LD3") (pin "1") (pinfunction "C_1") (pintype "passive"))
      (node (ref "T17") (pin "1") (pinfunction "G_1") (pintype "passive"))
      (node (ref "T18") (pin "3") (pinfunction "C_3") (pintype "passive"))
    )
    (net (code "15") (name "Net-(D12-A)") (class "Default")
      (node (ref "D12") (pin "2") (pinfunction "A_2") (pintype "passive"))
      (node (ref "R130") (pin "1") (pinfunction "1_1") (pintype "passive"))
    )
    (net (code "16") (name "Net-(D13-A)") (class "Default")
      (node (ref "D13") (pin "2") (pinfunction "A_2") (pintype "passive"))
      (node (ref "LD9") (pin "2") (pinfunction "A_2") (pintype "passive"))
      (node (ref "T19") (pin "3") (pinfunction "C_3") (pintype "passive"))
      (node (ref "T20") (pin "1") (pinfunction "G_1") (pintype "passive"))
    )
    (net (code "17") (name "Net-(IC20-+Vout)") (class "Default")
      (node (ref "C9") (pin "2") (pinfunction "2_2") (pintype "passive"))
      (node (ref "IC20") (pin "3") (pinfunction "+Vout_3") (pintype "power_in"))
      (node (ref "L6") (pin "1") (pinfunction "1_1") (pintype "passive"))
    )
    (net (code "18") (name "Net-(IC31--Vout)") (class "Default")
      (node (ref "C87") (pin "2") (pinfunction "2_2") (pintype "passive"))
      (node (ref "IC31") (pin "5") (pinfunction "-Vout_5") (pintype "power_in"))
      (node (ref "L9") (pin "1") (pinfunction "1_1") (pintype "passive"))
    )
    (net (code "19") (name "Net-(IC33-VADJ-Pad17)") (class "Default")
      (node (ref "IC33") (pin "17") (pinfunction "VADJ_17") (pintype "input"))
      (node (ref "IC33") (pin "8") (pinfunction "VADJ_8") (pintype "input"))
      (node (ref "R127") (pin "2") (pinfunction "2_2") (pintype "passive"))
      (node (ref "R134") (pin "2") (pinfunction "2_2") (pintype "passive"))
    )
    (net (code "20") (name "Net-(IC33-VREF-Pad16)") (class "Default")
      (node (ref "IC33") (pin "16") (pinfunction "VREF_16") (pintype "input"))
      (node (ref "IC33") (pin "9") (pinfunction "VREF_9") (pintype "input"))
      (node (ref "R127") (pin "1") (pinfunction "1_1") (pintype "passive"))
    )
    (net (code "21") (name "Net-(IC34-VADJ-Pad17)") (class "Default")
      (node (ref "IC34") (pin "17") (pinfunction "VADJ_17") (pintype "input"))
      (node (ref "IC34") (pin "8") (pinfunction "VADJ_8") (pintype "input"))
      (node (ref "R136") (pin "2") (pinfunction "2_2") (pintype "passive"))
      (node (ref "R137") (pin "2") (pinfunction "2_2") (pintype "passive"))
    )
    (net (code "22") (name "Net-(IC34-VREF-Pad16)") (class "Default")
      (node (ref "IC34") (pin "16") (pinfunction "VREF_16") (pintype "input"))
      (node (ref "IC34") (pin "9") (pinfunction "VREF_9") (pintype "input"))
      (node (ref "R136") (pin "1") (pinfunction "1_1") (pintype "passive"))
    )
    (net (code "23") (name "Net-(IC36-VADJ-Pad17)") (class "Default")
      (node (ref "IC36") (pin "17") (pinfunction "VADJ_17") (pintype "input"))
      (node (ref "IC36") (pin "8") (pinfunction "VADJ_8") (pintype "input"))
      (node (ref "R141") (pin "2") (pinfunction "2_2") (pintype "passive"))
      (node (ref "R144") (pin "2") (pinfunction "2_2") (pintype "passive"))
    )
    (net (code "24") (name "Net-(IC36-VREF-Pad16)") (class "Default")
      (node (ref "IC36") (pin "16") (pinfunction "VREF_16") (pintype "input"))
      (node (ref "IC36") (pin "9") (pinfunction "VREF_9") (pintype "input"))
      (node (ref "R141") (pin "1") (pinfunction "1_1") (pintype "passive"))
    )
    (net (code "25") (name "Net-(IC39-VADJ-Pad17)") (class "Default")
      (node (ref "IC39") (pin "17") (pinfunction "VADJ_17") (pintype "input"))
      (node (ref "IC39") (pin "8") (pinfunction "VADJ_8") (pintype "input"))
      (node (ref "R149") (pin "2") (pinfunction "2_2") (pintype "passive"))
      (node (ref "R168") (pin "2") (pinfunction "2_2") (pintype "passive"))
    )
    (net (code "26") (name "Net-(IC39-VREF-Pad16)") (class "Default")
      (node (ref "IC39") (pin "16") (pinfunction "VREF_16") (pintype "input"))
      (node (ref "IC39") (pin "9") (pinfunction "VREF_9") (pintype "input"))
      (node (ref "R149") (pin "1") (pinfunction "1_1") (pintype "passive"))
    )
    (net (code "27") (name "Net-(LD2-A)") (class "Default")
      (node (ref "LD2") (pin "2") (pinfunction "A_2") (pintype "passive"))
      (node (ref "R119") (pin "1") (pinfunction "1_1") (pintype "passive"))
    )
    (net (code "28") (name "Net-(LD3-A)") (class "Default")
      (node (ref "LD3") (pin "2") (pinfunction "A_2") (pintype "passive"))
      (node (ref "R121") (pin "1") (pinfunction "1_1") (pintype "passive"))
    )
    (net (code "29") (name "Net-(LD7-C)") (class "Default")
      (node (ref "LD7") (pin "1") (pinfunction "C_1") (pintype "passive"))
      (node (ref "R125") (pin "1") (pinfunction "1_1") (pintype "passive"))
    )
    (net (code "30") (name "Net-(LD9-C)") (class "Default")
      (node (ref "LD9") (pin "1") (pinfunction "C_1") (pintype "passive"))
      (node (ref "R131") (pin "2") (pinfunction "2_2") (pintype "passive"))
    )
    (net (code "31") (name "Net-(R120-Pad1)") (class "Default")
      (node (ref "R120") (pin "1") (pinfunction "1_1") (pintype "passive"))
      (node (ref "R123") (pin "2") (pinfunction "2_2") (pintype "passive"))
    )
    (net (code "32") (name "Net-(R121-Pad2)") (class "Default")
      (node (ref "R121") (pin "2") (pinfunction "2_2") (pintype "passive"))
      (node (ref "R122") (pin "1") (pinfunction "1_1") (pintype "passive"))
    )
    (net (code "33") (name "Net-(R128-Pad2)") (class "Default")
      (node (ref "R128") (pin "2") (pinfunction "2_2") (pintype "passive"))
      (node (ref "R131") (pin "1") (pinfunction "1_1") (pintype "passive"))
    )
    (net (code "34") (name "Net-(R129-Pad1)") (class "Default")
      (node (ref "R129") (pin "1") (pinfunction "1_1") (pintype "passive"))
      (node (ref "R133") (pin "2") (pinfunction "2_2") (pintype "passive"))
    )
    (net (code "35") (name "Net-(R167-Pad2)") (class "Default")
      (node (ref "R167") (pin "2") (pinfunction "2_2") (pintype "passive"))
      (node (ref "T21") (pin "4") (pinfunction "S_4") (pintype "passive"))
    )
    (net (code "36") (name "Net-(T17-D)") (class "Default")
      (node (ref "R123") (pin "1") (pinfunction "1_1") (pintype "passive"))
      (node (ref "T17") (pin "3") (pinfunction "D_3") (pintype "passive"))
    )
    (net (code "37") (name "Net-(T18-B)") (class "Default")
      (node (ref "R124") (pin "1") (pinfunction "1_1") (pintype "passive"))
      (node (ref "R126") (pin "2") (pinfunction "2_2") (pintype "passive"))
      (node (ref "T18") (pin "1") (pinfunction "B_1") (pintype "passive"))
    )
    (net (code "38") (name "Net-(T19-E)") (class "Default")
      (node (ref "R130") (pin "2") (pinfunction "2_2") (pintype "passive"))
      (node (ref "R132") (pin "2") (pinfunction "2_2") (pintype "passive"))
      (node (ref "T19") (pin "2") (pinfunction "E_2") (pintype "passive"))
    )
    (net (code "39") (name "Net-(T20-D)") (class "Default")
      (node (ref "R133") (pin "1") (pinfunction "1_1") (pintype "passive"))
      (node (ref "T20") (pin "3") (pinfunction "D_3") (pintype "passive"))
    )
    (net (code "40") (name "Net-(T22-B)") (class "Default")
      (node (ref "R202") (pin "2") (pinfunction "2_2") (pintype "passive"))
      (node (ref "T22") (pin "1") (pinfunction "B_1") (pintype "passive"))
    )
    (net (code "41") (name "Net-(T22-C)") (class "Default")
      (node (ref "R167") (pin "1") (pinfunction "1_1") (pintype "passive"))
      (node (ref "R201") (pin "2") (pinfunction "2_2") (pintype "passive"))
      (node (ref "T22") (pin "3") (pinfunction "C_3") (pintype "passive"))
    )
    (net (code "42") (name "P12V0") (class "Default")
      (node (ref "C156") (pin "1") (pinfunction "1_1") (pintype "passive"))
      (node (ref "D12") (pin "1") (pinfunction "C_1") (pintype "passive"))
      (node (ref "R124") (pin "2") (pinfunction "2_2") (pintype "passive"))
      (node (ref "R201") (pin "1") (pinfunction "1_1") (pintype "passive"))
      (node (ref "T21") (pin "1") (pinfunction "S_1") (pintype "passive"))
      (node (ref "T21") (pin "2") (pinfunction "S_2") (pintype "passive"))
      (node (ref "T21") (pin "3") (pinfunction "S_3") (pintype "passive"))
    )
    (net (code "43") (name "P12V0_SW") (class "Default")
      (node (ref "C134") (pin "1") (pinfunction "1_1") (pintype "passive"))
      (node (ref "C135") (pin "2") (pinfunction "2_2") (pintype "passive"))
      (node (ref "C137") (pin "2") (pinfunction "2_2") (pintype "passive"))
      (node (ref "C150") (pin "1") (pinfunction "1_1") (pintype "passive"))
      (node (ref "C151") (pin "2") (pinfunction "2_2") (pintype "passive"))
      (node (ref "C157") (pin "2") (pinfunction "2_2") (pintype "passive"))
      (node (ref "C41") (pin "2") (pinfunction "2_2") (pintype "passive"))
      (node (ref "C84") (pin "2") (pinfunction "2_2") (pintype "passive"))
      (node (ref "IC20") (pin "2") (pinfunction "+Vin_2") (pintype "power_in"))
      (node (ref "IC31") (pin "2") (pinfunction "+Vin_2") (pintype "power_in"))
      (node (ref "IC33") (pin "22") (pinfunction "+Vin_22") (pintype "power_in"))
      (node (ref "IC33") (pin "23") (pinfunction "+Vin_23") (pintype "power_in"))
      (node (ref "IC34") (pin "22") (pinfunction "+Vin_22") (pintype "power_in"))
      (node (ref "IC34") (pin "23") (pinfunction "+Vin_23") (pintype "power_in"))
      (node (ref "IC36") (pin "22") (pinfunction "+Vin_22") (pintype "power_in"))
      (node (ref "IC36") (pin "23") (pinfunction "+Vin_23") (pintype "power_in"))
      (node (ref "IC39") (pin "22") (pinfunction "+Vin_22") (pintype "power_in"))
      (node (ref "IC39") (pin "23") (pinfunction "+Vin_23") (pintype "power_in"))
      (node (ref "T21") (pin "5") (pinfunction "D_5") (pintype "passive"))
      (node (ref "T21") (pin "6") (pinfunction "D_6") (pintype "passive"))
      (node (ref "T21") (pin "7") (pinfunction "D_7") (pintype "passive"))
      (node (ref "T21") (pin "8") (pinfunction "D_8") (pintype "passive"))
      (node (ref "TP22") (pin "1") (pinfunction "1_1") (pintype "bidirectional"))
    )
    (net (code "44") (name "P24VA") (class "Default")
      (node (ref "C13") (pin "2") (pinfunction "2_2") (pintype "passive"))
      (node (ref "C14") (pin "1") (pinfunction "1_1") (pintype "passive"))
      (node (ref "D6") (pin "1") (pinfunction "C_1") (pintype "passive"))
      (node (ref "L8") (pin "2") (pinfunction "2_2") (pintype "passive"))
      (node (ref "R119") (pin "2") (pinfunction "2_2") (pintype "passive"))
      (node (ref "TP8") (pin "1") (pinfunction "1_1") (pintype "bidirectional"))
    )
  )
)
